# schematic_easyeda.net
KiCad netlist of a schematic drawn in EasyEDA
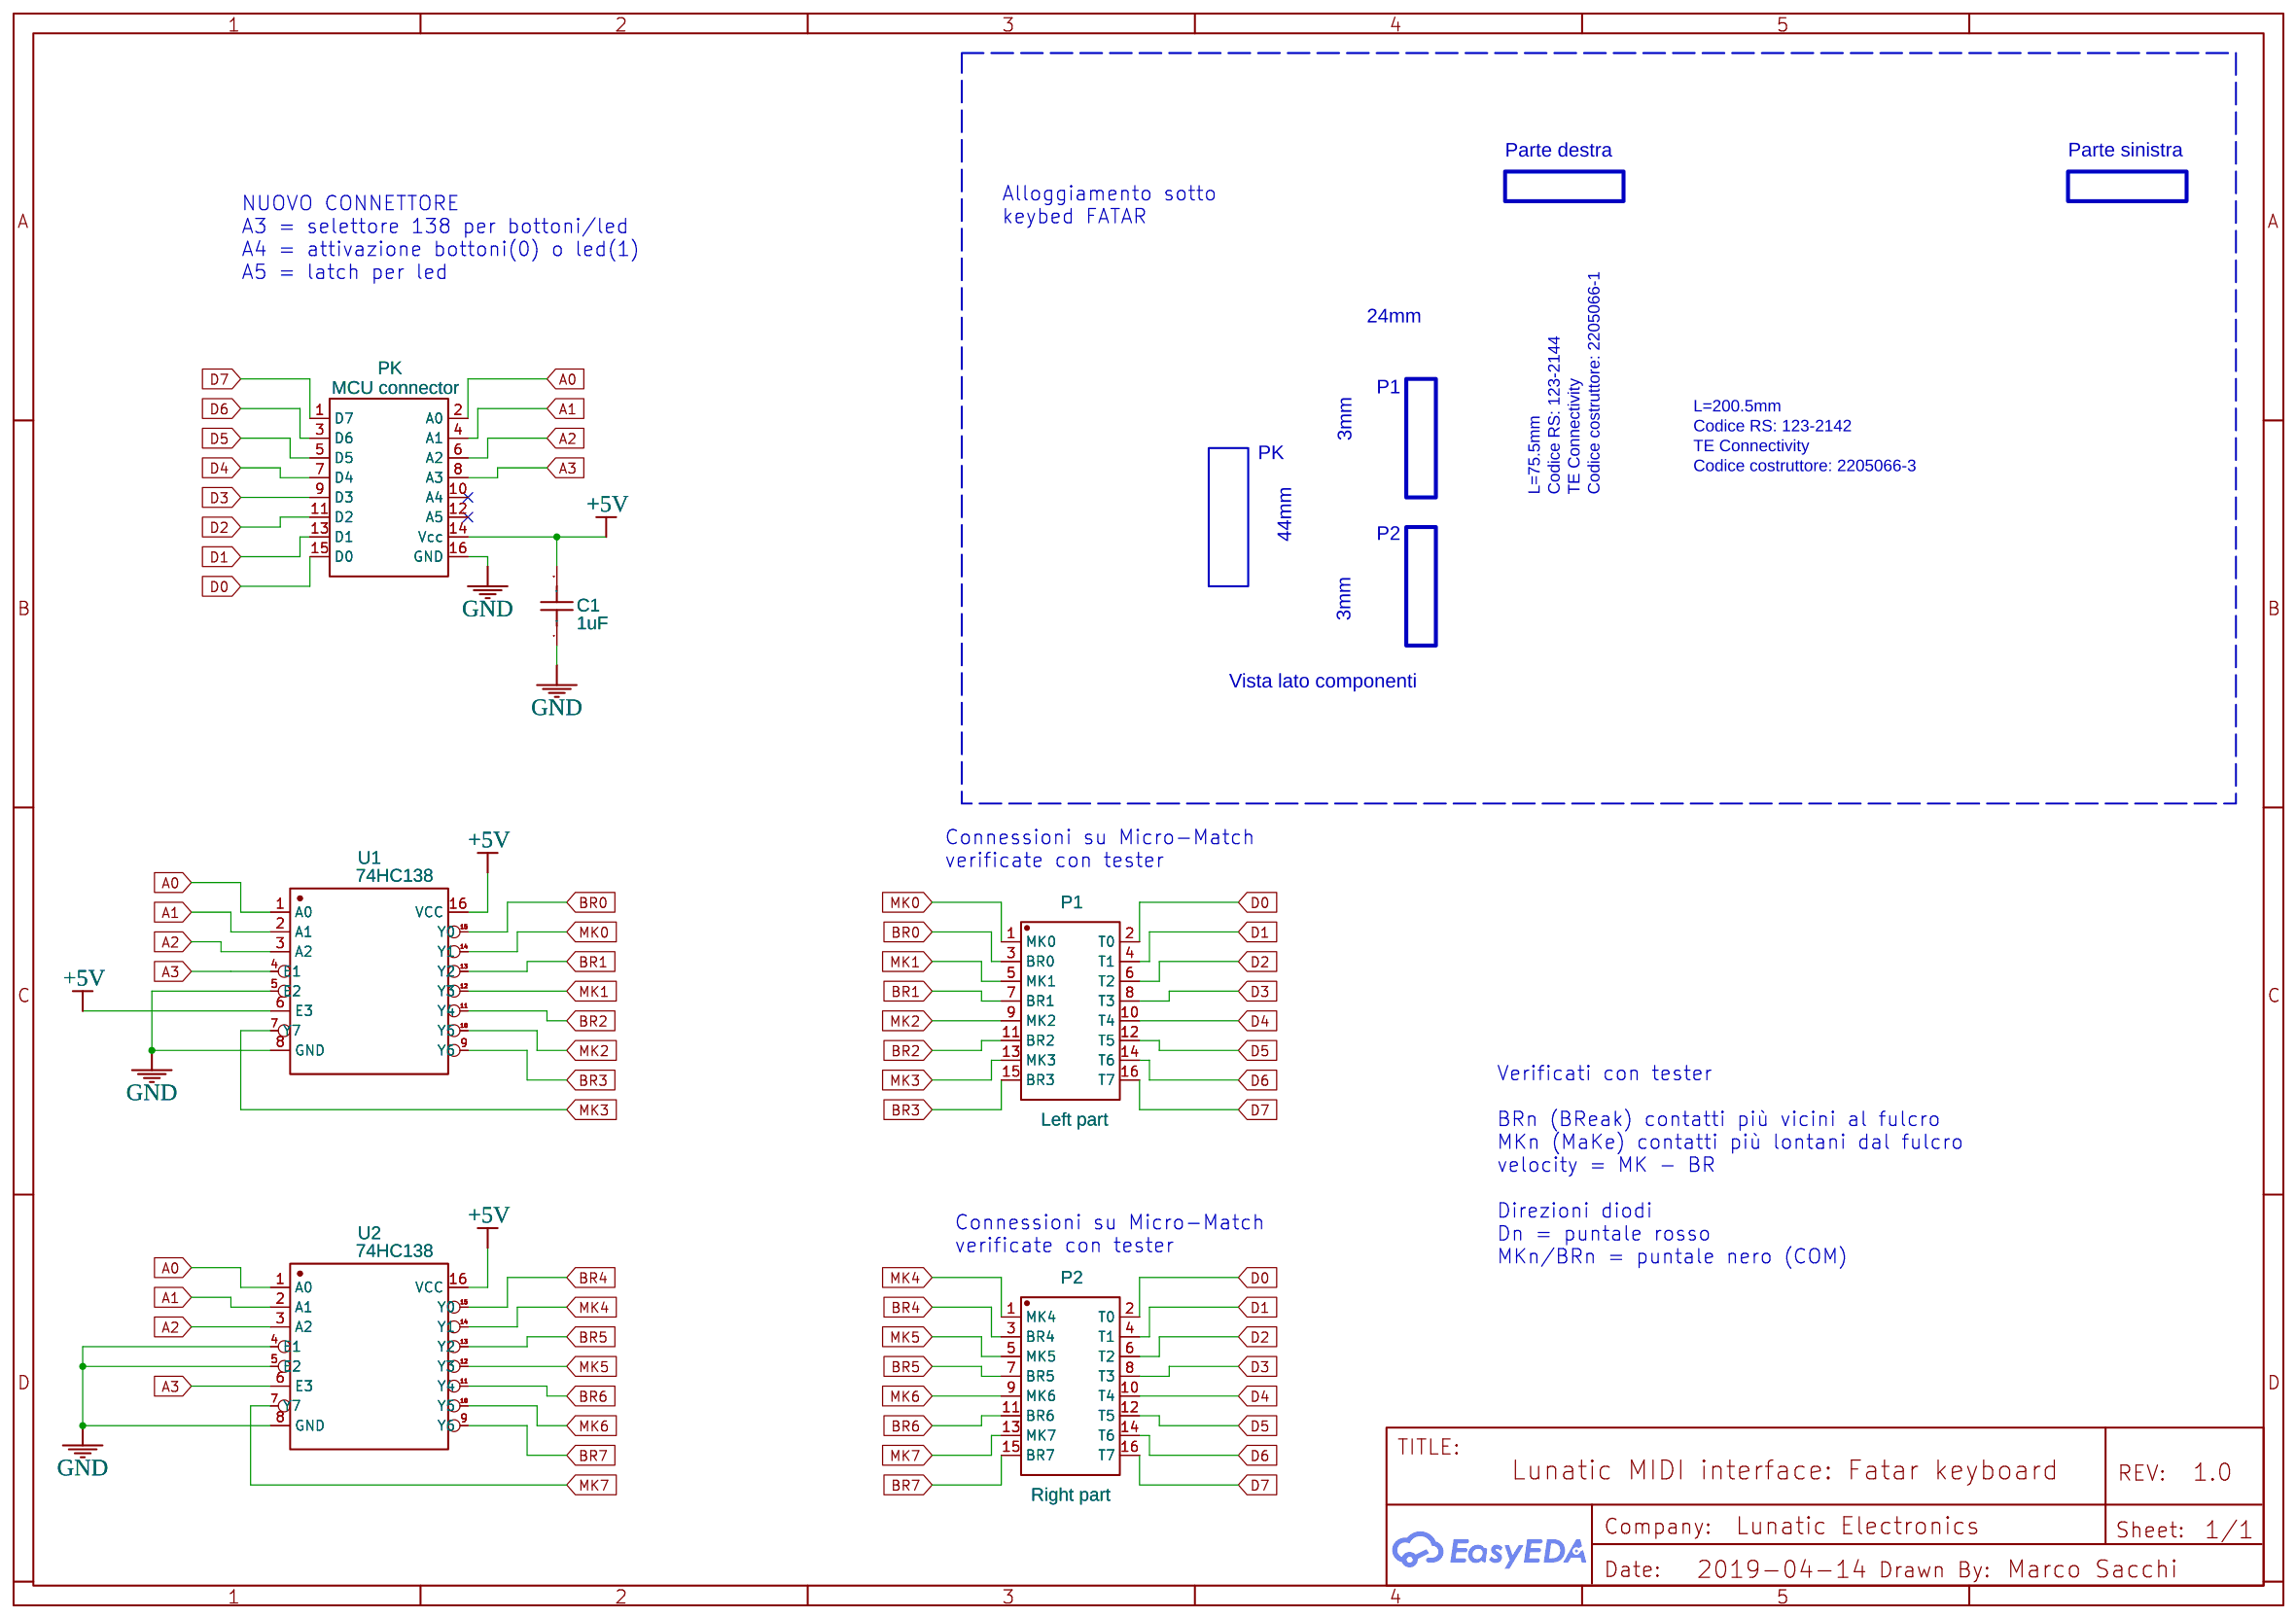
[diagram p0: schematic sheet]

(export (version "E")
  (design (tool "Eeschema 10.0.6"))
  (components
    (comp (ref "C1")
      (value "1uF")
      (fields (field (name "BOM_Manufacturer Part") "?"))
      (libsource (lib "") (part "Cap_RAD-0.1_US"))
    )
    (comp (ref "P1")
      (value "Left part")
      (fields
        (field (name "BOM_Manufacturer Part") "1-215079-6")
        (field (name "BOM_Supplier Part") "680-4980")
      )
      (libsource (lib "") (part "Unknown_510_460"))
    )
    (comp (ref "P2")
      (value "Right part")
      (fields
        (field (name "BOM_Manufacturer Part") "1-215079-6")
        (field (name "BOM_Supplier Part") "680-4980")
      )
      (libsource (lib "") (part "Unknown_510_650"))
    )
    (comp (ref "PK")
      (value "MCU connector")
      (fields (field (name "BOM_Manufacturer Part") "GEM"))
      (libsource (lib "") (part "Unknown_180_235"))
    )
    (comp (ref "U1")
      (value "74HC138")
      (fields (field (name "BOM_Supplier Part") "C5194"))
      (libsource (lib "") (part "Unknown_180_490"))
    )
    (comp (ref "U2")
      (value "74HC138")
      (fields (field (name "BOM_Supplier Part") "C5194"))
      (libsource (lib "") (part "Unknown_180_680"))
    )
  )
  (nets
    (net (code "1") (name "+5V") (class "Default")
      (node (ref "C1") (pin "2") (pinfunction "2_2") (pintype "unspecified"))
      (node (ref "PK") (pin "14") (pinfunction "Vcc_14") (pintype "passive"))
      (node (ref "U1") (pin "16") (pinfunction "VCC_16") (pintype "unspecified"))
      (node (ref "U1") (pin "6") (pinfunction "E3_6") (pintype "unspecified"))
      (node (ref "U2") (pin "16") (pinfunction "VCC_16") (pintype "unspecified"))
    )
    (net (code "2") (name "A0") (class "Default")
      (node (ref "PK") (pin "2") (pinfunction "A0_2") (pintype "output"))
      (node (ref "U1") (pin "1") (pinfunction "A0_1") (pintype "unspecified"))
      (node (ref "U2") (pin "1") (pinfunction "A0_1") (pintype "unspecified"))
    )
    (net (code "3") (name "A1") (class "Default")
      (node (ref "PK") (pin "4") (pinfunction "A1_4") (pintype "output"))
      (node (ref "U1") (pin "2") (pinfunction "A1_2") (pintype "unspecified"))
      (node (ref "U2") (pin "2") (pinfunction "A1_2") (pintype "unspecified"))
    )
    (net (code "4") (name "A2") (class "Default")
      (node (ref "PK") (pin "6") (pinfunction "A2_6") (pintype "output"))
      (node (ref "U1") (pin "3") (pinfunction "A2_3") (pintype "unspecified"))
      (node (ref "U2") (pin "3") (pinfunction "A2_3") (pintype "unspecified"))
    )
    (net (code "5") (name "A3") (class "Default")
      (node (ref "PK") (pin "8") (pinfunction "A3_8") (pintype "output"))
      (node (ref "U1") (pin "4") (pinfunction "E1_4") (pintype "unspecified"))
      (node (ref "U2") (pin "6") (pinfunction "E3_6") (pintype "unspecified"))
    )
    (net (code "6") (name "BR0") (class "Default")
      (node (ref "P1") (pin "3") (pinfunction "BR0_3") (pintype "unspecified"))
      (node (ref "U1") (pin "15") (pinfunction "Y0_15") (pintype "unspecified"))
    )
    (net (code "7") (name "BR1") (class "Default")
      (node (ref "P1") (pin "7") (pinfunction "BR1_7") (pintype "unspecified"))
      (node (ref "U1") (pin "13") (pinfunction "Y2_13") (pintype "unspecified"))
    )
    (net (code "8") (name "BR2") (class "Default")
      (node (ref "P1") (pin "11") (pinfunction "BR2_11") (pintype "unspecified"))
      (node (ref "U1") (pin "11") (pinfunction "Y4_11") (pintype "unspecified"))
    )
    (net (code "9") (name "BR3") (class "Default")
      (node (ref "P1") (pin "15") (pinfunction "BR3_15") (pintype "unspecified"))
      (node (ref "U1") (pin "9") (pinfunction "Y6_9") (pintype "unspecified"))
    )
    (net (code "10") (name "BR4") (class "Default")
      (node (ref "P2") (pin "3") (pinfunction "BR4_3") (pintype "unspecified"))
      (node (ref "U2") (pin "15") (pinfunction "Y0_15") (pintype "unspecified"))
    )
    (net (code "11") (name "BR5") (class "Default")
      (node (ref "P2") (pin "7") (pinfunction "BR5_7") (pintype "unspecified"))
      (node (ref "U2") (pin "13") (pinfunction "Y2_13") (pintype "unspecified"))
    )
    (net (code "12") (name "BR6") (class "Default")
      (node (ref "P2") (pin "11") (pinfunction "BR6_11") (pintype "unspecified"))
      (node (ref "U2") (pin "11") (pinfunction "Y4_11") (pintype "unspecified"))
    )
    (net (code "13") (name "BR7") (class "Default")
      (node (ref "P2") (pin "15") (pinfunction "BR7_15") (pintype "unspecified"))
      (node (ref "U2") (pin "9") (pinfunction "Y6_9") (pintype "unspecified"))
    )
    (net (code "14") (name "D0") (class "Default")
      (node (ref "P1") (pin "2") (pinfunction "T0_2") (pintype "unspecified"))
      (node (ref "P2") (pin "2") (pinfunction "T0_2") (pintype "unspecified"))
      (node (ref "PK") (pin "15") (pinfunction "D0_15") (pintype "bidirectional"))
    )
    (net (code "15") (name "D1") (class "Default")
      (node (ref "P1") (pin "4") (pinfunction "T1_4") (pintype "unspecified"))
      (node (ref "P2") (pin "4") (pinfunction "T1_4") (pintype "unspecified"))
      (node (ref "PK") (pin "13") (pinfunction "D1_13") (pintype "bidirectional"))
    )
    (net (code "16") (name "D2") (class "Default")
      (node (ref "P1") (pin "6") (pinfunction "T2_6") (pintype "unspecified"))
      (node (ref "P2") (pin "6") (pinfunction "T2_6") (pintype "unspecified"))
      (node (ref "PK") (pin "11") (pinfunction "D2_11") (pintype "bidirectional"))
    )
    (net (code "17") (name "D3") (class "Default")
      (node (ref "P1") (pin "8") (pinfunction "T3_8") (pintype "unspecified"))
      (node (ref "P2") (pin "8") (pinfunction "T3_8") (pintype "unspecified"))
      (node (ref "PK") (pin "9") (pinfunction "D3_9") (pintype "bidirectional"))
    )
    (net (code "18") (name "D4") (class "Default")
      (node (ref "P1") (pin "10") (pinfunction "T4_10") (pintype "unspecified"))
      (node (ref "P2") (pin "10") (pinfunction "T4_10") (pintype "unspecified"))
      (node (ref "PK") (pin "7") (pinfunction "D4_7") (pintype "bidirectional"))
    )
    (net (code "19") (name "D5") (class "Default")
      (node (ref "P1") (pin "12") (pinfunction "T5_12") (pintype "unspecified"))
      (node (ref "P2") (pin "12") (pinfunction "T5_12") (pintype "unspecified"))
      (node (ref "PK") (pin "5") (pinfunction "D5_5") (pintype "bidirectional"))
    )
    (net (code "20") (name "D6") (class "Default")
      (node (ref "P1") (pin "14") (pinfunction "T6_14") (pintype "unspecified"))
      (node (ref "P2") (pin "14") (pinfunction "T6_14") (pintype "unspecified"))
      (node (ref "PK") (pin "3") (pinfunction "D6_3") (pintype "bidirectional"))
    )
    (net (code "21") (name "D7") (class "Default")
      (node (ref "P1") (pin "16") (pinfunction "T7_16") (pintype "unspecified"))
      (node (ref "P2") (pin "16") (pinfunction "T7_16") (pintype "unspecified"))
      (node (ref "PK") (pin "1") (pinfunction "D7_1") (pintype "bidirectional"))
    )
    (net (code "22") (name "GND") (class "Default")
      (node (ref "C1") (pin "1") (pinfunction "1_1") (pintype "unspecified"))
      (node (ref "PK") (pin "16") (pinfunction "GND_16") (pintype "passive"))
      (node (ref "U1") (pin "5") (pinfunction "E2_5") (pintype "unspecified"))
      (node (ref "U1") (pin "8") (pinfunction "GND_8") (pintype "unspecified"))
      (node (ref "U2") (pin "4") (pinfunction "E1_4") (pintype "unspecified"))
      (node (ref "U2") (pin "5") (pinfunction "E2_5") (pintype "unspecified"))
      (node (ref "U2") (pin "8") (pinfunction "GND_8") (pintype "unspecified"))
    )
    (net (code "23") (name "MK0") (class "Default")
      (node (ref "P1") (pin "1") (pinfunction "MK0_1") (pintype "unspecified"))
      (node (ref "U1") (pin "14") (pinfunction "Y1_14") (pintype "unspecified"))
    )
    (net (code "24") (name "MK1") (class "Default")
      (node (ref "P1") (pin "5") (pinfunction "MK1_5") (pintype "unspecified"))
      (node (ref "U1") (pin "12") (pinfunction "Y3_12") (pintype "unspecified"))
    )
    (net (code "25") (name "MK2") (class "Default")
      (node (ref "P1") (pin "9") (pinfunction "MK2_9") (pintype "unspecified"))
      (node (ref "U1") (pin "10") (pinfunction "Y5_10") (pintype "unspecified"))
    )
    (net (code "26") (name "MK3") (class "Default")
      (node (ref "P1") (pin "13") (pinfunction "MK3_13") (pintype "unspecified"))
      (node (ref "U1") (pin "7") (pinfunction "Y7_7") (pintype "unspecified"))
    )
    (net (code "27") (name "MK4") (class "Default")
      (node (ref "P2") (pin "1") (pinfunction "MK4_1") (pintype "unspecified"))
      (node (ref "U2") (pin "14") (pinfunction "Y1_14") (pintype "unspecified"))
    )
    (net (code "28") (name "MK5") (class "Default")
      (node (ref "P2") (pin "5") (pinfunction "MK5_5") (pintype "unspecified"))
      (node (ref "U2") (pin "12") (pinfunction "Y3_12") (pintype "unspecified"))
    )
    (net (code "29") (name "MK6") (class "Default")
      (node (ref "P2") (pin "9") (pinfunction "MK6_9") (pintype "unspecified"))
      (node (ref "U2") (pin "10") (pinfunction "Y5_10") (pintype "unspecified"))
    )
    (net (code "30") (name "MK7") (class "Default")
      (node (ref "P2") (pin "13") (pinfunction "MK7_13") (pintype "unspecified"))
      (node (ref "U2") (pin "7") (pinfunction "Y7_7") (pintype "unspecified"))
    )
    (net (code "31") (name "unconnected-(PK-A4-Pad10)") (class "Default")
      (node (ref "PK") (pin "10") (pinfunction "A4_10") (pintype "output+no_connect"))
    )
    (net (code "32") (name "unconnected-(PK-A5-Pad12)") (class "Default")
      (node (ref "PK") (pin "12") (pinfunction "A5_12") (pintype "output+no_connect"))
    )
  )
)
